# MCU.net
KiCad netlist of a schematic drawn in Altium Designer
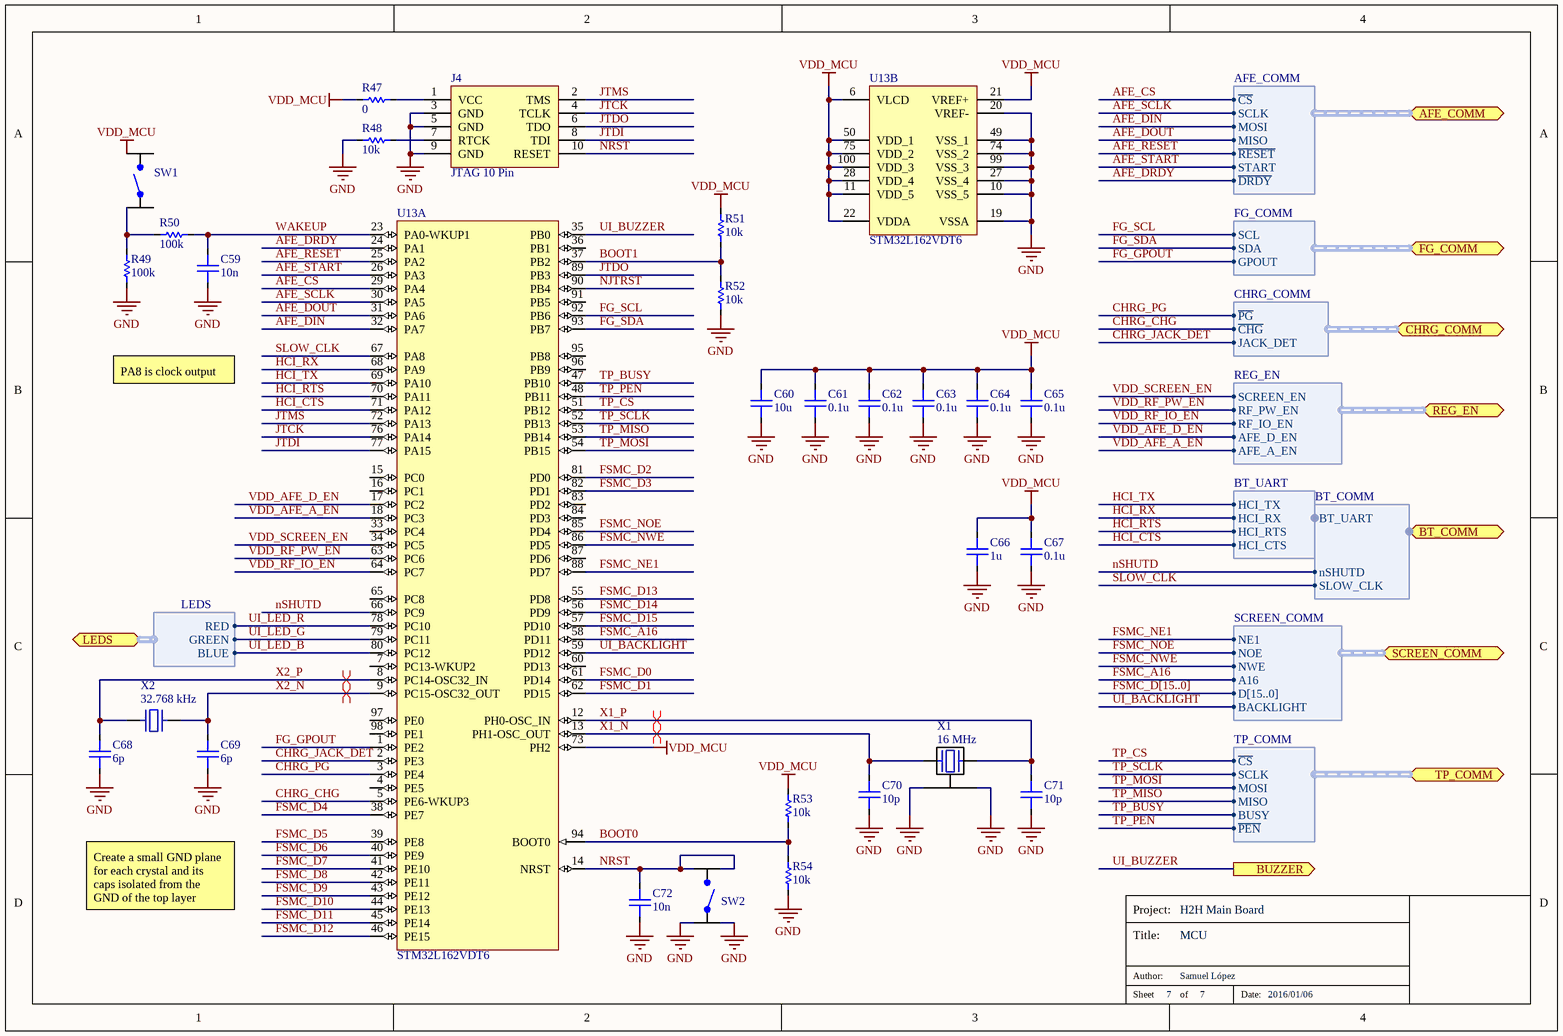
[diagram p0: MCU.SchDoc]

(export (version "E")
  (design (tool "Eeschema 10.0.6"))
  (components
    (comp (ref "C59")
      (value "10n")
      (footprint "C0603")
      (description "Capacitor")
      (libsource (lib "Misc") (part "Capacitor"))
    )
    (comp (ref "C60")
      (value "10u")
      (footprint "C0603")
      (description "Capacitor")
      (libsource (lib "Misc") (part "Capacitor"))
    )
    (comp (ref "C61")
      (value "0.1u")
      (footprint "C0603")
      (description "Capacitor")
      (libsource (lib "Misc") (part "Capacitor"))
    )
    (comp (ref "C62")
      (value "0.1u")
      (footprint "C0603")
      (description "Capacitor")
      (libsource (lib "Misc") (part "Capacitor"))
    )
    (comp (ref "C63")
      (value "0.1u")
      (footprint "C0603")
      (description "Capacitor")
      (libsource (lib "Misc") (part "Capacitor"))
    )
    (comp (ref "C64")
      (value "0.1u")
      (footprint "C0603")
      (description "Capacitor")
      (libsource (lib "Misc") (part "Capacitor"))
    )
    (comp (ref "C65")
      (value "0.1u")
      (footprint "C0603")
      (description "Capacitor")
      (libsource (lib "Misc") (part "Capacitor"))
    )
    (comp (ref "C66")
      (value "1u")
      (footprint "C0603")
      (description "Capacitor")
      (libsource (lib "Misc") (part "Capacitor"))
    )
    (comp (ref "C67")
      (value "0.1u")
      (footprint "C0603")
      (description "Capacitor")
      (libsource (lib "Misc") (part "Capacitor"))
    )
    (comp (ref "C68")
      (value "6p")
      (footprint "C0603")
      (description "Capacitor")
      (libsource (lib "Misc") (part "Capacitor"))
    )
    (comp (ref "C69")
      (value "6p")
      (footprint "C0603")
      (description "Capacitor")
      (libsource (lib "Misc") (part "Capacitor"))
    )
    (comp (ref "C70")
      (value "10p")
      (footprint "C0603")
      (description "Capacitor")
      (libsource (lib "Misc") (part "Capacitor"))
    )
    (comp (ref "C71")
      (value "10p")
      (footprint "C0603")
      (description "Capacitor")
      (libsource (lib "Misc") (part "Capacitor"))
    )
    (comp (ref "C72")
      (value "10n")
      (footprint "C0603")
      (description "Capacitor")
      (libsource (lib "Misc") (part "Capacitor"))
    )
    (comp (ref "J4")
      (value "JTAG 10 Pin")
      (footprint "3220-10-0200-00")
      (description "Conn - JTAG, Header, Male, Right Angle, 10 Pin, 1.27mm Pitch, ARM Standard")
      (libsource (lib "Conn") (part "3220-10-0200-00"))
    )
    (comp (ref "R47")
      (value "0")
      (footprint "R0603")
      (description "Resistor")
      (libsource (lib "Misc") (part "Resistor"))
    )
    (comp (ref "R48")
      (value "10k")
      (footprint "R0603")
      (description "Resistor")
      (libsource (lib "Misc") (part "Resistor"))
    )
    (comp (ref "R49")
      (value "100k")
      (footprint "R0603")
      (description "Resistor")
      (libsource (lib "Misc") (part "Resistor"))
    )
    (comp (ref "R50")
      (value "100k")
      (footprint "R0603")
      (description "Resistor")
      (libsource (lib "Misc") (part "Resistor"))
    )
    (comp (ref "R51")
      (value "10k")
      (footprint "R0603")
      (description "Resistor")
      (libsource (lib "Misc") (part "Resistor"))
    )
    (comp (ref "R52")
      (value "10k")
      (footprint "R0603")
      (description "Resistor")
      (libsource (lib "Misc") (part "Resistor"))
    )
    (comp (ref "R53")
      (value "10k")
      (footprint "R0603")
      (description "Resistor")
      (libsource (lib "Misc") (part "Resistor"))
    )
    (comp (ref "R54")
      (value "10k")
      (footprint "R0603")
      (description "Resistor")
      (libsource (lib "Misc") (part "Resistor"))
    )
    (comp (ref "SW1")
      (value "WS-TASU 436331045822")
      (footprint "WS-TASU 436331045822")
      (description "Switch - Tactile, Off-Mom, SPST, Side-Actuated")
      (libsource (lib "H2H") (part "WS-TASU 436331045822"))
    )
    (comp (ref "SW2")
      (value "EVQ-Q2K01W")
      (footprint "EVQ-Q2K01W")
      (description "Switch - Tactile, Off-Mom, SPST")
      (libsource (lib "H2H") (part "EVQ-Q2K01W"))
    )
    (comp (ref "U13")
      (value "STM32L162VDT6")
      (footprint "STM-LQFP100_N")
      (fields (field (name "MANUFACTURER") "STMicroelectronics"))
      (libsource (lib "STMicroelectronics STM32 L1") (part "STM32L162VDT6"))
    )
    (comp (ref "X1")
      (value "ABM3B-16.000MHZ-10-1-U")
      (footprint "ABM3B-16.000MHZ-10-1-U")
      (description "Crystal - 16 MHz")
      (fields (field (name "FREQUENCY") "16 MHz"))
      (libsource (lib "H2H") (part "ABM3B-16.000MHZ-10-1-U"))
    )
    (comp (ref "X2")
      (value "ABS07-120-32.768KHZ-T")
      (footprint "ABS07-120-32.768KHZ-T")
      (description "Crystal - 32.768 kHz")
      (fields (field (name "FREQUENCY") "32.768 kHz"))
      (libsource (lib "H2H") (part "ABS07-120-32.768KHZ-T"))
    )
  )
  (nets
    (net (code "9") (name "/AFE_CS") (class "Default")
      (node (ref "U13") (pin "29") (pinfunction "PA4_29") (pintype "bidirectional"))
    )
    (net (code "10") (name "/AFE_DIN") (class "Default")
      (node (ref "U13") (pin "32") (pinfunction "PA7_32") (pintype "bidirectional"))
    )
    (net (code "11") (name "/AFE_DOUT") (class "Default")
      (node (ref "U13") (pin "31") (pinfunction "PA6_31") (pintype "bidirectional"))
    )
    (net (code "12") (name "/AFE_DRDY") (class "Default")
      (node (ref "U13") (pin "24") (pinfunction "PA1_24") (pintype "bidirectional"))
    )
    (net (code "13") (name "/AFE_RESET") (class "Default")
      (node (ref "U13") (pin "25") (pinfunction "PA2_25") (pintype "bidirectional"))
    )
    (net (code "14") (name "/AFE_SCLK") (class "Default")
      (node (ref "U13") (pin "30") (pinfunction "PA5_30") (pintype "bidirectional"))
    )
    (net (code "15") (name "/AFE_START") (class "Default")
      (node (ref "U13") (pin "26") (pinfunction "PA3_26") (pintype "bidirectional"))
    )
    (net (code "16") (name "/BOOT0") (class "Default")
      (node (ref "R53") (pin "1") (pinfunction "1_1") (pintype "passive"))
      (node (ref "R54") (pin "2") (pinfunction "2_2") (pintype "passive"))
      (node (ref "U13") (pin "94") (pinfunction "BOOT0_94") (pintype "input"))
    )
    (net (code "17") (name "/BOOT1") (class "Default")
      (node (ref "R51") (pin "1") (pinfunction "1_1") (pintype "passive"))
      (node (ref "R52") (pin "2") (pinfunction "2_2") (pintype "passive"))
      (node (ref "U13") (pin "37") (pinfunction "PB2_37") (pintype "bidirectional"))
    )
    (net (code "18") (name "/CHRG_CHG") (class "Default")
      (node (ref "U13") (pin "5") (pinfunction "PE6-WKUP3_5") (pintype "bidirectional"))
    )
    (net (code "19") (name "/CHRG_JACK_DET") (class "Default")
      (node (ref "U13") (pin "2") (pinfunction "PE3_2") (pintype "bidirectional"))
    )
    (net (code "20") (name "/CHRG_PG") (class "Default")
      (node (ref "U13") (pin "3") (pinfunction "PE4_3") (pintype "bidirectional"))
    )
    (net (code "21") (name "/FG_GPOUT") (class "Default")
      (node (ref "U13") (pin "1") (pinfunction "PE2_1") (pintype "bidirectional"))
    )
    (net (code "22") (name "/FG_SCL") (class "Default")
      (node (ref "U13") (pin "92") (pinfunction "PB6_92") (pintype "bidirectional"))
    )
    (net (code "23") (name "/FG_SDA") (class "Default")
      (node (ref "U13") (pin "93") (pinfunction "PB7_93") (pintype "bidirectional"))
    )
    (net (code "24") (name "/FSMC_A16") (class "Default")
      (node (ref "U13") (pin "58") (pinfunction "PD11_58") (pintype "bidirectional"))
    )
    (net (code "25") (name "/FSMC_D0") (class "Default")
      (node (ref "U13") (pin "61") (pinfunction "PD14_61") (pintype "bidirectional"))
    )
    (net (code "26") (name "/FSMC_D1") (class "Default")
      (node (ref "U13") (pin "62") (pinfunction "PD15_62") (pintype "bidirectional"))
    )
    (net (code "27") (name "/FSMC_D2") (class "Default")
      (node (ref "U13") (pin "81") (pinfunction "PD0_81") (pintype "bidirectional"))
    )
    (net (code "28") (name "/FSMC_D3") (class "Default")
      (node (ref "U13") (pin "82") (pinfunction "PD1_82") (pintype "bidirectional"))
    )
    (net (code "29") (name "/FSMC_D4") (class "Default")
      (node (ref "U13") (pin "38") (pinfunction "PE7_38") (pintype "bidirectional"))
    )
    (net (code "30") (name "/FSMC_D5") (class "Default")
      (node (ref "U13") (pin "39") (pinfunction "PE8_39") (pintype "bidirectional"))
    )
    (net (code "31") (name "/FSMC_D6") (class "Default")
      (node (ref "U13") (pin "40") (pinfunction "PE9_40") (pintype "bidirectional"))
    )
    (net (code "32") (name "/FSMC_D7") (class "Default")
      (node (ref "U13") (pin "41") (pinfunction "PE10_41") (pintype "bidirectional"))
    )
    (net (code "33") (name "/FSMC_D8") (class "Default")
      (node (ref "U13") (pin "42") (pinfunction "PE11_42") (pintype "bidirectional"))
    )
    (net (code "34") (name "/FSMC_D9") (class "Default")
      (node (ref "U13") (pin "43") (pinfunction "PE12_43") (pintype "bidirectional"))
    )
    (net (code "35") (name "/FSMC_D10") (class "Default")
      (node (ref "U13") (pin "44") (pinfunction "PE13_44") (pintype "bidirectional"))
    )
    (net (code "36") (name "/FSMC_D11") (class "Default")
      (node (ref "U13") (pin "45") (pinfunction "PE14_45") (pintype "bidirectional"))
    )
    (net (code "37") (name "/FSMC_D12") (class "Default")
      (node (ref "U13") (pin "46") (pinfunction "PE15_46") (pintype "bidirectional"))
    )
    (net (code "38") (name "/FSMC_D13") (class "Default")
      (node (ref "U13") (pin "55") (pinfunction "PD8_55") (pintype "bidirectional"))
    )
    (net (code "39") (name "/FSMC_D14") (class "Default")
      (node (ref "U13") (pin "56") (pinfunction "PD9_56") (pintype "bidirectional"))
    )
    (net (code "40") (name "/FSMC_D15") (class "Default")
      (node (ref "U13") (pin "57") (pinfunction "PD10_57") (pintype "bidirectional"))
    )
    (net (code "41") (name "/FSMC_NE1") (class "Default")
      (node (ref "U13") (pin "88") (pinfunction "PD7_88") (pintype "bidirectional"))
    )
    (net (code "42") (name "/FSMC_NOE") (class "Default")
      (node (ref "U13") (pin "85") (pinfunction "PD4_85") (pintype "bidirectional"))
    )
    (net (code "43") (name "/FSMC_NWE") (class "Default")
      (node (ref "U13") (pin "86") (pinfunction "PD5_86") (pintype "bidirectional"))
    )
    (net (code "44") (name "/HCI_CTS") (class "Default")
      (node (ref "U13") (pin "71") (pinfunction "PA12_71") (pintype "bidirectional"))
    )
    (net (code "45") (name "/HCI_RTS") (class "Default")
      (node (ref "U13") (pin "70") (pinfunction "PA11_70") (pintype "bidirectional"))
    )
    (net (code "46") (name "/HCI_RX") (class "Default")
      (node (ref "U13") (pin "68") (pinfunction "PA9_68") (pintype "bidirectional"))
    )
    (net (code "47") (name "/HCI_TX") (class "Default")
      (node (ref "U13") (pin "69") (pinfunction "PA10_69") (pintype "bidirectional"))
    )
    (net (code "48") (name "/JTCK") (class "Default")
      (node (ref "J4") (pin "4") (pinfunction "TCLK_4") (pintype "passive"))
      (node (ref "U13") (pin "76") (pinfunction "PA14_76") (pintype "bidirectional"))
    )
    (net (code "49") (name "/JTDI") (class "Default")
      (node (ref "J4") (pin "8") (pinfunction "TDI_8") (pintype "passive"))
      (node (ref "U13") (pin "77") (pinfunction "PA15_77") (pintype "bidirectional"))
    )
    (net (code "50") (name "/JTDO") (class "Default")
      (node (ref "J4") (pin "6") (pinfunction "TDO_6") (pintype "passive"))
      (node (ref "U13") (pin "89") (pinfunction "PB3_89") (pintype "bidirectional"))
    )
    (net (code "51") (name "/JTMS") (class "Default")
      (node (ref "J4") (pin "2") (pinfunction "TMS_2") (pintype "passive"))
      (node (ref "U13") (pin "72") (pinfunction "PA13_72") (pintype "bidirectional"))
    )
    (net (code "52") (name "/NJTRST") (class "Default")
      (node (ref "U13") (pin "90") (pinfunction "PB4_90") (pintype "bidirectional"))
    )
    (net (code "53") (name "/NRST") (class "Default")
      (node (ref "C72") (pin "2") (pinfunction "2_2") (pintype "passive"))
      (node (ref "J4") (pin "10") (pinfunction "RESET_10") (pintype "passive"))
      (node (ref "SW2") (pin "3") (pinfunction "B2_3") (pintype "passive"))
      (node (ref "SW2") (pin "4") (pinfunction "B1_4") (pintype "passive"))
      (node (ref "U13") (pin "14") (pinfunction "NRST_14") (pintype "bidirectional"))
    )
    (net (code "55") (name "/SLOW_CLK") (class "Default")
      (node (ref "U13") (pin "67") (pinfunction "PA8_67") (pintype "bidirectional"))
    )
    (net (code "56") (name "/TP_BUSY") (class "Default")
      (node (ref "U13") (pin "47") (pinfunction "PB10_47") (pintype "bidirectional"))
    )
    (net (code "57") (name "/TP_CS") (class "Default")
      (node (ref "U13") (pin "51") (pinfunction "PB12_51") (pintype "bidirectional"))
    )
    (net (code "58") (name "/TP_MISO") (class "Default")
      (node (ref "U13") (pin "53") (pinfunction "PB14_53") (pintype "bidirectional"))
    )
    (net (code "59") (name "/TP_MOSI") (class "Default")
      (node (ref "U13") (pin "54") (pinfunction "PB15_54") (pintype "bidirectional"))
    )
    (net (code "60") (name "/TP_PEN") (class "Default")
      (node (ref "U13") (pin "48") (pinfunction "PB11_48") (pintype "bidirectional"))
    )
    (net (code "61") (name "/TP_SCLK") (class "Default")
      (node (ref "U13") (pin "52") (pinfunction "PB13_52") (pintype "bidirectional"))
    )
    (net (code "62") (name "/UI_BACKLIGHT") (class "Default")
      (node (ref "U13") (pin "59") (pinfunction "PD12_59") (pintype "bidirectional"))
    )
    (net (code "63") (name "/UI_BUZZER") (class "Default")
      (node (ref "U13") (pin "35") (pinfunction "PB0_35") (pintype "bidirectional"))
    )
    (net (code "64") (name "/UI_LED_B") (class "Default")
      (node (ref "U13") (pin "80") (pinfunction "PC12_80") (pintype "bidirectional"))
    )
    (net (code "65") (name "/UI_LED_G") (class "Default")
      (node (ref "U13") (pin "79") (pinfunction "PC11_79") (pintype "bidirectional"))
    )
    (net (code "66") (name "/UI_LED_R") (class "Default")
      (node (ref "U13") (pin "78") (pinfunction "PC10_78") (pintype "bidirectional"))
    )
    (net (code "67") (name "/VDD_AFE_A_EN") (class "Default")
      (node (ref "U13") (pin "18") (pinfunction "PC3_18") (pintype "bidirectional"))
    )
    (net (code "68") (name "/VDD_AFE_D_EN") (class "Default")
      (node (ref "U13") (pin "17") (pinfunction "PC2_17") (pintype "bidirectional"))
    )
    (net (code "69") (name "/VDD_RF_IO_EN") (class "Default")
      (node (ref "U13") (pin "64") (pinfunction "PC7_64") (pintype "bidirectional"))
    )
    (net (code "70") (name "/VDD_RF_PW_EN") (class "Default")
      (node (ref "U13") (pin "63") (pinfunction "PC6_63") (pintype "bidirectional"))
    )
    (net (code "71") (name "/VDD_SCREEN_EN") (class "Default")
      (node (ref "U13") (pin "34") (pinfunction "PC5_34") (pintype "bidirectional"))
    )
    (net (code "72") (name "/WAKEUP") (class "Default")
      (node (ref "C59") (pin "2") (pinfunction "2_2") (pintype "passive"))
      (node (ref "R50") (pin "2") (pinfunction "2_2") (pintype "passive"))
      (node (ref "U13") (pin "23") (pinfunction "PA0-WKUP1_23") (pintype "bidirectional"))
    )
    (net (code "73") (name "/X1_N") (class "Default")
      (node (ref "C70") (pin "2") (pinfunction "2_2") (pintype "passive"))
      (node (ref "U13") (pin "13") (pinfunction "PH1-OSC_OUT_13") (pintype "bidirectional"))
      (node (ref "X1") (pin "1") (pinfunction "1_1") (pintype "passive"))
    )
    (net (code "74") (name "/X1_P") (class "Default")
      (node (ref "C71") (pin "2") (pinfunction "2_2") (pintype "passive"))
      (node (ref "U13") (pin "12") (pinfunction "PH0-OSC_IN_12") (pintype "bidirectional"))
      (node (ref "X1") (pin "3") (pinfunction "3_3") (pintype "passive"))
    )
    (net (code "75") (name "/X2_N") (class "Default")
      (node (ref "C69") (pin "2") (pinfunction "2_2") (pintype "passive"))
      (node (ref "U13") (pin "9") (pinfunction "PC15-OSC32_OUT_9") (pintype "bidirectional"))
      (node (ref "X2") (pin "1") (pinfunction "1_1") (pintype "passive"))
    )
    (net (code "76") (name "/X2_P") (class "Default")
      (node (ref "C68") (pin "2") (pinfunction "2_2") (pintype "passive"))
      (node (ref "U13") (pin "8") (pinfunction "PC14-OSC32_IN_8") (pintype "bidirectional"))
      (node (ref "X2") (pin "2") (pinfunction "2_2") (pintype "passive"))
    )
    (net (code "77") (name "/nSHUTD") (class "Default")
      (node (ref "U13") (pin "66") (pinfunction "PC9_66") (pintype "bidirectional"))
    )
    (net (code "86") (name "GND") (class "Default")
      (node (ref "C59") (pin "1") (pinfunction "1_1") (pintype "passive"))
      (node (ref "C60") (pin "1") (pinfunction "1_1") (pintype "passive"))
      (node (ref "C61") (pin "1") (pinfunction "1_1") (pintype "passive"))
      (node (ref "C62") (pin "1") (pinfunction "1_1") (pintype "passive"))
      (node (ref "C63") (pin "1") (pinfunction "1_1") (pintype "passive"))
      (node (ref "C64") (pin "1") (pinfunction "1_1") (pintype "passive"))
      (node (ref "C65") (pin "1") (pinfunction "1_1") (pintype "passive"))
      (node (ref "C66") (pin "1") (pinfunction "1_1") (pintype "passive"))
      (node (ref "C67") (pin "1") (pinfunction "1_1") (pintype "passive"))
      (node (ref "C68") (pin "1") (pinfunction "1_1") (pintype "passive"))
      (node (ref "C69") (pin "1") (pinfunction "1_1") (pintype "passive"))
      (node (ref "C70") (pin "1") (pinfunction "1_1") (pintype "passive"))
      (node (ref "C71") (pin "1") (pinfunction "1_1") (pintype "passive"))
      (node (ref "C72") (pin "1") (pinfunction "1_1") (pintype "passive"))
      (node (ref "J4") (pin "3") (pinfunction "GND_3") (pintype "passive"))
      (node (ref "J4") (pin "5") (pinfunction "GND_5") (pintype "passive"))
      (node (ref "J4") (pin "9") (pinfunction "GND_9") (pintype "passive"))
      (node (ref "R48") (pin "1") (pinfunction "1_1") (pintype "passive"))
      (node (ref "R49") (pin "1") (pinfunction "1_1") (pintype "passive"))
      (node (ref "R52") (pin "1") (pinfunction "1_1") (pintype "passive"))
      (node (ref "R54") (pin "1") (pinfunction "1_1") (pintype "passive"))
      (node (ref "SW2") (pin "1") (pinfunction "A1_1") (pintype "passive"))
      (node (ref "SW2") (pin "2") (pinfunction "A2_2") (pintype "passive"))
      (node (ref "U13") (pin "10") (pinfunction "VSS_5_10") (pintype "power_in"))
      (node (ref "U13") (pin "19") (pinfunction "VSSA_19") (pintype "power_in"))
      (node (ref "U13") (pin "20") (pinfunction "VREF-_20") (pintype "power_in"))
      (node (ref "U13") (pin "27") (pinfunction "VSS_4_27") (pintype "power_in"))
      (node (ref "U13") (pin "49") (pinfunction "VSS_1_49") (pintype "power_in"))
      (node (ref "U13") (pin "74") (pinfunction "VSS_2_74") (pintype "power_in"))
      (node (ref "U13") (pin "99") (pinfunction "VSS_3_99") (pintype "power_in"))
      (node (ref "X1") (pin "2") (pinfunction "2_2") (pintype "passive"))
      (node (ref "X1") (pin "4") (pinfunction "4_4") (pintype "passive"))
    )
    (net (code "87") (name "Net-(J4-RTCK)") (class "Default")
      (node (ref "J4") (pin "7") (pinfunction "RTCK_7") (pintype "passive"))
      (node (ref "R48") (pin "2") (pinfunction "2_2") (pintype "passive"))
    )
    (net (code "88") (name "Net-(J4-VCC)") (class "Default")
      (node (ref "J4") (pin "1") (pinfunction "VCC_1") (pintype "passive"))
      (node (ref "R47") (pin "2") (pinfunction "2_2") (pintype "passive"))
    )
    (net (code "89") (name "Net-(R49-Pad2)") (class "Default")
      (node (ref "R49") (pin "2") (pinfunction "2_2") (pintype "passive"))
      (node (ref "R50") (pin "1") (pinfunction "1_1") (pintype "passive"))
      (node (ref "SW1") (pin "1") (pinfunction "1_1") (pintype "passive"))
    )
    (net (code "90") (name "VDD_MCU") (class "Default")
      (node (ref "C60") (pin "2") (pinfunction "2_2") (pintype "passive"))
      (node (ref "C61") (pin "2") (pinfunction "2_2") (pintype "passive"))
      (node (ref "C62") (pin "2") (pinfunction "2_2") (pintype "passive"))
      (node (ref "C63") (pin "2") (pinfunction "2_2") (pintype "passive"))
      (node (ref "C64") (pin "2") (pinfunction "2_2") (pintype "passive"))
      (node (ref "C65") (pin "2") (pinfunction "2_2") (pintype "passive"))
      (node (ref "C66") (pin "2") (pinfunction "2_2") (pintype "passive"))
      (node (ref "C67") (pin "2") (pinfunction "2_2") (pintype "passive"))
      (node (ref "R47") (pin "1") (pinfunction "1_1") (pintype "passive"))
      (node (ref "R51") (pin "2") (pinfunction "2_2") (pintype "passive"))
      (node (ref "R53") (pin "2") (pinfunction "2_2") (pintype "passive"))
      (node (ref "SW1") (pin "2") (pinfunction "2_2") (pintype "passive"))
      (node (ref "U13") (pin "100") (pinfunction "VDD_3_100") (pintype "power_in"))
      (node (ref "U13") (pin "11") (pinfunction "VDD_5_11") (pintype "power_in"))
      (node (ref "U13") (pin "21") (pinfunction "VREF+_21") (pintype "power_in"))
      (node (ref "U13") (pin "22") (pinfunction "VDDA_22") (pintype "power_in"))
      (node (ref "U13") (pin "28") (pinfunction "VDD_4_28") (pintype "power_in"))
      (node (ref "U13") (pin "50") (pinfunction "VDD_1_50") (pintype "power_in"))
      (node (ref "U13") (pin "6") (pinfunction "VLCD_6") (pintype "power_in"))
      (node (ref "U13") (pin "73") (pinfunction "PH2_73") (pintype "bidirectional"))
      (node (ref "U13") (pin "75") (pinfunction "VDD_2_75") (pintype "power_in"))
    )
    (net (code "91") (name "unconnected-(SW1-Pad3)") (class "Default")
      (node (ref "SW1") (pin "3") (pinfunction "3_3") (pintype "passive"))
    )
    (net (code "92") (name "unconnected-(SW1-Pad4)") (class "Default")
      (node (ref "SW1") (pin "4") (pinfunction "4_4") (pintype "passive"))
    )
    (net (code "93") (name "unconnected-(U13A-PB1-Pad36)") (class "Default")
      (node (ref "U13") (pin "36") (pinfunction "PB1_36") (pintype "bidirectional"))
    )
    (net (code "94") (name "unconnected-(U13A-PB5-Pad91)") (class "Default")
      (node (ref "U13") (pin "91") (pinfunction "PB5_91") (pintype "bidirectional"))
    )
    (net (code "95") (name "unconnected-(U13A-PB8-Pad95)") (class "Default")
      (node (ref "U13") (pin "95") (pinfunction "PB8_95") (pintype "bidirectional"))
    )
    (net (code "96") (name "unconnected-(U13A-PB9-Pad96)") (class "Default")
      (node (ref "U13") (pin "96") (pinfunction "PB9_96") (pintype "bidirectional"))
    )
    (net (code "97") (name "unconnected-(U13A-PC0-Pad15)") (class "Default")
      (node (ref "U13") (pin "15") (pinfunction "PC0_15") (pintype "bidirectional"))
    )
    (net (code "98") (name "unconnected-(U13A-PC1-Pad16)") (class "Default")
      (node (ref "U13") (pin "16") (pinfunction "PC1_16") (pintype "bidirectional"))
    )
    (net (code "99") (name "unconnected-(U13A-PC4-Pad33)") (class "Default")
      (node (ref "U13") (pin "33") (pinfunction "PC4_33") (pintype "bidirectional"))
    )
    (net (code "100") (name "unconnected-(U13A-PC8-Pad65)") (class "Default")
      (node (ref "U13") (pin "65") (pinfunction "PC8_65") (pintype "bidirectional"))
    )
    (net (code "101") (name "unconnected-(U13A-PC13-WKUP2-Pad7)") (class "Default")
      (node (ref "U13") (pin "7") (pinfunction "PC13-WKUP2_7") (pintype "bidirectional"))
    )
    (net (code "102") (name "unconnected-(U13A-PD2-Pad83)") (class "Default")
      (node (ref "U13") (pin "83") (pinfunction "PD2_83") (pintype "bidirectional"))
    )
    (net (code "103") (name "unconnected-(U13A-PD3-Pad84)") (class "Default")
      (node (ref "U13") (pin "84") (pinfunction "PD3_84") (pintype "bidirectional"))
    )
    (net (code "104") (name "unconnected-(U13A-PD6-Pad87)") (class "Default")
      (node (ref "U13") (pin "87") (pinfunction "PD6_87") (pintype "bidirectional"))
    )
    (net (code "105") (name "unconnected-(U13A-PD13-Pad60)") (class "Default")
      (node (ref "U13") (pin "60") (pinfunction "PD13_60") (pintype "bidirectional"))
    )
    (net (code "106") (name "unconnected-(U13A-PE0-Pad97)") (class "Default")
      (node (ref "U13") (pin "97") (pinfunction "PE0_97") (pintype "bidirectional"))
    )
    (net (code "107") (name "unconnected-(U13A-PE1-Pad98)") (class "Default")
      (node (ref "U13") (pin "98") (pinfunction "PE1_98") (pintype "bidirectional"))
    )
    (net (code "108") (name "unconnected-(U13A-PE5-Pad4)") (class "Default")
      (node (ref "U13") (pin "4") (pinfunction "PE5_4") (pintype "bidirectional"))
    )
  )
)
